# SD.net
KiCad netlist of a schematic drawn in Altium Designer
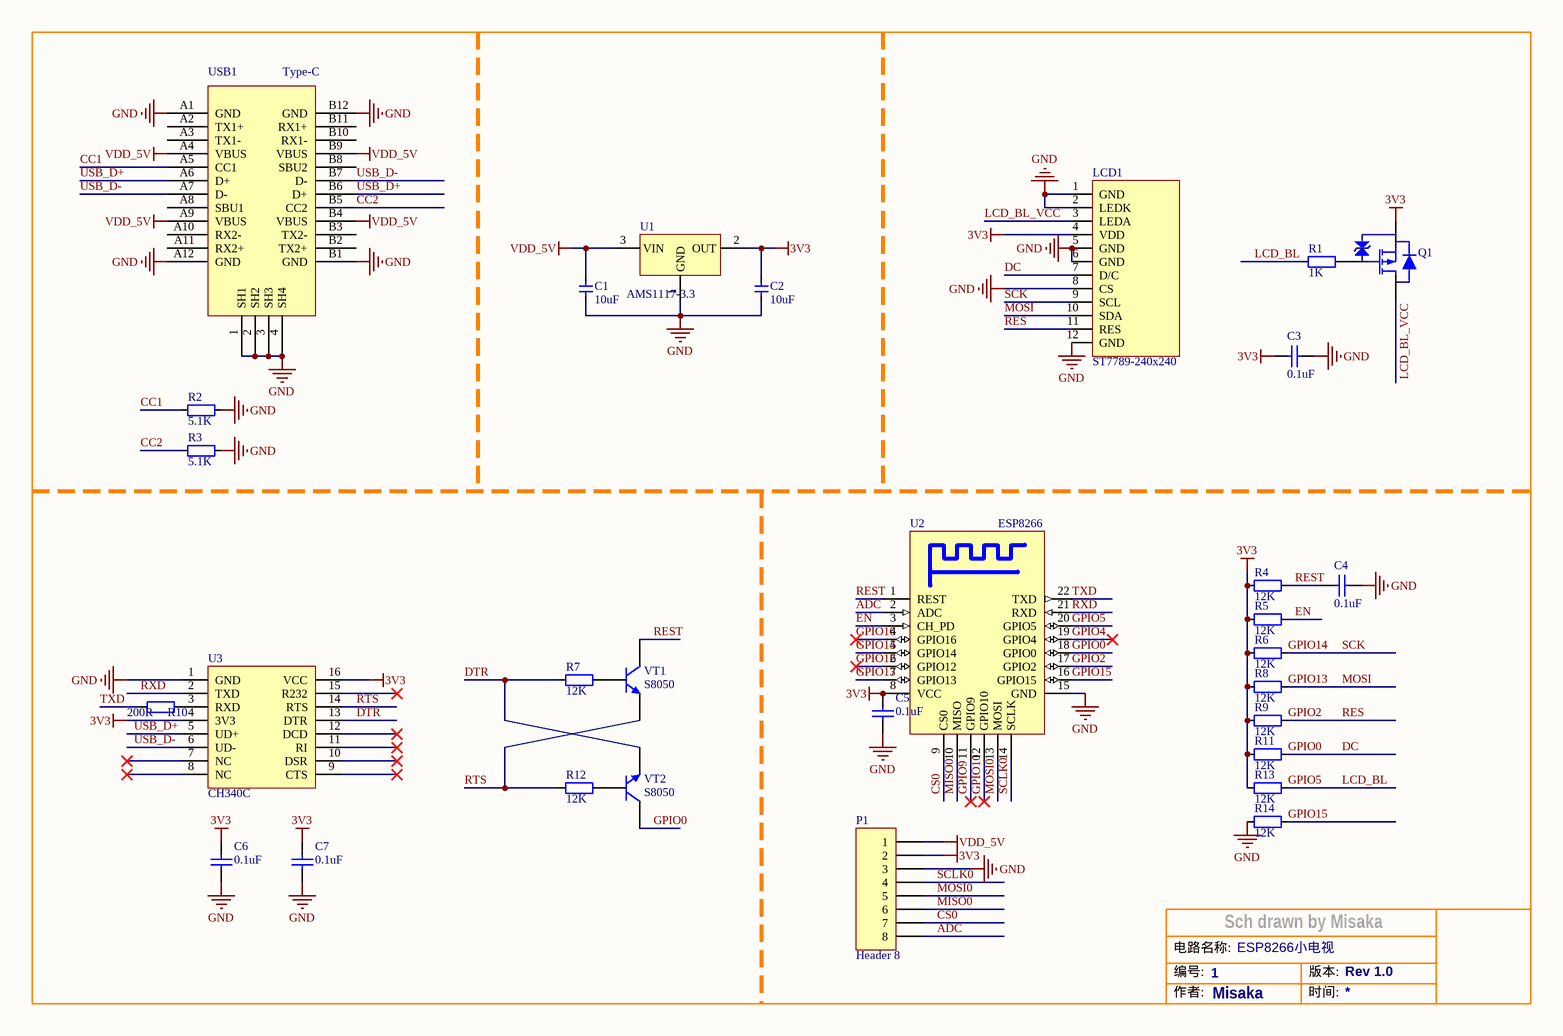
[diagram p0: SD²原理图.SchDoc]

(export (version "E")
  (design (tool "Eeschema 10.0.6"))
  (components
    (comp (ref "C1")
      (value "10uF")
      (footprint "C_0603")
      (description "Capacitor")
      (libsource (lib "MyPcbLib") (part "电容-0402"))
    )
    (comp (ref "C2")
      (value "10uF")
      (footprint "C_0603")
      (description "Capacitor")
      (libsource (lib "MyPcbLib") (part "电容-0402"))
    )
    (comp (ref "C3")
      (value "0.1uF")
      (footprint "C_0603")
      (description "Capacitor")
      (fields (field (name "PUBLISHER") "Altium Limited"))
      (libsource (lib "Miscellaneous Devices") (part "Cap"))
    )
    (comp (ref "C4")
      (value "0.1uF")
      (footprint "C_0603")
      (description "Capacitor")
      (fields (field (name "PUBLISHER") "Altium Limited"))
      (libsource (lib "Miscellaneous Devices") (part "Cap"))
    )
    (comp (ref "C5")
      (value "0.1uF")
      (footprint "C_0603")
      (description "Capacitor")
      (fields (field (name "PUBLISHER") "Altium Limited"))
      (libsource (lib "Miscellaneous Devices") (part "Cap"))
    )
    (comp (ref "C6")
      (value "0.1uF")
      (footprint "C_0603")
      (description "Capacitor")
      (fields (field (name "PUBLISHER") "Altium Limited"))
      (libsource (lib "Miscellaneous Devices") (part "Cap"))
    )
    (comp (ref "C7")
      (value "0.1uF")
      (footprint "C_0603")
      (description "Capacitor")
      (fields (field (name "PUBLISHER") "Altium Limited"))
      (libsource (lib "Miscellaneous Devices") (part "Cap"))
    )
    (comp (ref "LCD1")
      (value "ST7789-240x240")
      (footprint "LCD-240X240-12P")
      (description "显示屏")
      (libsource (lib "mLib") (part "LCD-240x240"))
    )
    (comp (ref "P1")
      (value "Header 8")
      (footprint "FFC_0.5_8")
      (description "Header, 8-Pin")
      (fields (field (name "PUBLISHER") "Altium Limited"))
      (libsource (lib "Miscellaneous Connectors") (part "Header 8"))
    )
    (comp (ref "Q1")
      (value "AO3415A")
      (footprint "SOT-23-y")
      (description "MOSFET")
      (fields (field (name "PUBLISHER") "Altium Limited"))
      (libsource (lib "MyPcbLib") (part "AO3415A"))
    )
    (comp (ref "R1")
      (value "1K")
      (footprint "R_0603")
      (description "Resistor")
      (libsource (lib "") (part "电阻-0402_2"))
    )
    (comp (ref "R2")
      (value "5.1K")
      (footprint "R_0603")
      (description "Resistor")
      (libsource (lib "MyPcbLib") (part "电阻-0402"))
    )
    (comp (ref "R3")
      (value "5.1K")
      (footprint "R_0603")
      (description "Resistor")
      (libsource (lib "MyPcbLib") (part "电阻-0402"))
    )
    (comp (ref "R4")
      (value "12K")
      (footprint "R_0603")
      (description "Resistor")
      (libsource (lib "MyPcbLib") (part "电阻-0402"))
    )
    (comp (ref "R5")
      (value "12K")
      (footprint "R_0603")
      (description "Resistor")
      (libsource (lib "MyPcbLib") (part "电阻-0402"))
    )
    (comp (ref "R6")
      (value "12K")
      (footprint "R_0603")
      (description "Resistor")
      (libsource (lib "MyPcbLib") (part "电阻-0402"))
    )
    (comp (ref "R7")
      (value "12K")
      (footprint "R_0603")
      (description "Resistor")
      (libsource (lib "MyPcbLib") (part "电阻-0402"))
    )
    (comp (ref "R8")
      (value "12K")
      (footprint "R_0603")
      (description "Resistor")
      (libsource (lib "MyPcbLib") (part "电阻-0402"))
    )
    (comp (ref "R9")
      (value "12K")
      (footprint "R_0603")
      (description "Resistor")
      (libsource (lib "MyPcbLib") (part "电阻-0402"))
    )
    (comp (ref "R10")
      (value "200R")
      (footprint "R_0603")
      (description "Resistor")
      (libsource (lib "") (part "电阻-0402_1"))
    )
    (comp (ref "R11")
      (value "12K")
      (footprint "R_0603")
      (description "Resistor")
      (libsource (lib "MyPcbLib") (part "电阻-0402"))
    )
    (comp (ref "R12")
      (value "12K")
      (footprint "R_0603")
      (description "Resistor")
      (libsource (lib "MyPcbLib") (part "电阻-0402"))
    )
    (comp (ref "R13")
      (value "12K")
      (footprint "R_0603")
      (description "Resistor")
      (libsource (lib "MyPcbLib") (part "电阻-0402"))
    )
    (comp (ref "R14")
      (value "12K")
      (footprint "R_0603")
      (description "Resistor")
      (libsource (lib "MyPcbLib") (part "电阻-0402"))
    )
    (comp (ref "U1") (value "AMS1117-3.3") (footprint "SOT223_y") (libsource (lib "数控电源") (part "LM317M")))
    (comp (ref "U2") (value "ESP8266") (footprint "8266") (libsource (lib "Misaka") (part "ESP8266")))
    (comp (ref "U3") (value "CH340C") (footprint "SOP16N_N") (libsource (lib "Misaka") (part "CH340C")))
    (comp (ref "USB1")
      (value "Type-C")
      (footprint "Misaka:Type-C-TOP")
      (libsource (lib "MyPcbLib") (part "USB-Type-C-TOP"))
    )
    (comp (ref "VT1")
      (value "S8050")
      (footprint "SOT-23-y")
      (description "Surface mount NPN transistor, package SOT-23")
      (libsource (lib "MyPcbLib") (part "SMT_TRIODE_NPN"))
    )
    (comp (ref "VT2")
      (value "S8050")
      (footprint "SOT-23-y")
      (description "Surface mount NPN transistor, package SOT-23")
      (libsource (lib "MyPcbLib") (part "SMT_TRIODE_NPN"))
    )
  )
  (nets
    (net (code "1") (name "/ADC") (class "Default")
      (node (ref "P1") (pin "8") (pinfunction "8_8") (pintype "passive"))
      (node (ref "U2") (pin "2") (pinfunction "ADC_2") (pintype "input"))
    )
    (net (code "2") (name "/CC1") (class "Default")
      (node (ref "R2") (pin "1") (pinfunction "1_1") (pintype "passive"))
      (node (ref "USB1") (pin "A5") (pinfunction "CC1_A5") (pintype "passive"))
    )
    (net (code "3") (name "/CC2") (class "Default")
      (node (ref "R3") (pin "1") (pinfunction "1_1") (pintype "passive"))
      (node (ref "USB1") (pin "B5") (pinfunction "CC2_B5") (pintype "passive"))
    )
    (net (code "4") (name "/CS0") (class "Default")
      (node (ref "P1") (pin "7") (pinfunction "7_7") (pintype "passive"))
      (node (ref "U2") (pin "9") (pinfunction "CS0_9") (pintype "passive"))
    )
    (net (code "5") (name "/DC") (class "Default")
      (node (ref "LCD1") (pin "7") (pinfunction "D/C_7") (pintype "passive"))
      (node (ref "R11") (pin "2") (pinfunction "2_2") (pintype "passive"))
      (node (ref "U2") (pin "18") (pinfunction "GPIO0_18") (pintype "bidirectional"))
      (node (ref "VT2") (pin "3") (pinfunction "C_3") (pintype "passive"))
    )
    (net (code "6") (name "/DTR") (class "Default")
      (node (ref "R7") (pin "1") (pinfunction "1_1") (pintype "passive"))
      (node (ref "U3") (pin "13") (pinfunction "DTR_13") (pintype "passive"))
      (node (ref "VT2") (pin "2") (pinfunction "E_2") (pintype "passive"))
    )
    (net (code "7") (name "/EN") (class "Default")
      (node (ref "R5") (pin "2") (pinfunction "2_2") (pintype "passive"))
      (node (ref "U2") (pin "3") (pinfunction "CH_PD_3") (pintype "input"))
    )
    (net (code "8") (name "/GPIO2") (class "Default")
      (node (ref "LCD1") (pin "11") (pinfunction "RES_11") (pintype "passive"))
      (node (ref "R9") (pin "2") (pinfunction "2_2") (pintype "passive"))
      (node (ref "U2") (pin "17") (pinfunction "GPIO2_17") (pintype "bidirectional"))
    )
    (net (code "9") (name "/GPIO4") (class "Default")
      (node (ref "U2") (pin "19") (pinfunction "GPIO4_19") (pintype "bidirectional+no_connect"))
    )
    (net (code "10") (name "/GPIO5") (class "Default")
      (node (ref "R1") (pin "1") (pinfunction "1_1") (pintype "passive"))
      (node (ref "R13") (pin "2") (pinfunction "2_2") (pintype "passive"))
      (node (ref "U2") (pin "20") (pinfunction "GPIO5_20") (pintype "bidirectional"))
    )
    (net (code "11") (name "/GPIO9") (class "Default")
      (node (ref "U2") (pin "11") (pinfunction "GPIO9_11") (pintype "passive+no_connect"))
    )
    (net (code "12") (name "/GPIO10") (class "Default")
      (node (ref "U2") (pin "12") (pinfunction "GPIO10_12") (pintype "passive+no_connect"))
    )
    (net (code "13") (name "/GPIO12") (class "Default")
      (node (ref "U2") (pin "6") (pinfunction "GPIO12_6") (pintype "bidirectional+no_connect"))
    )
    (net (code "14") (name "/GPIO13") (class "Default")
      (node (ref "LCD1") (pin "10") (pinfunction "SDA_10") (pintype "passive"))
      (node (ref "R8") (pin "2") (pinfunction "2_2") (pintype "passive"))
      (node (ref "U2") (pin "7") (pinfunction "GPIO13_7") (pintype "bidirectional"))
    )
    (net (code "15") (name "/GPIO14") (class "Default")
      (node (ref "LCD1") (pin "9") (pinfunction "SCL_9") (pintype "passive"))
      (node (ref "R6") (pin "2") (pinfunction "2_2") (pintype "passive"))
      (node (ref "U2") (pin "5") (pinfunction "GPIO14_5") (pintype "bidirectional"))
    )
    (net (code "16") (name "/GPIO15") (class "Default")
      (node (ref "R14") (pin "2") (pinfunction "2_2") (pintype "passive"))
      (node (ref "U2") (pin "16") (pinfunction "GPIO15_16") (pintype "bidirectional"))
    )
    (net (code "17") (name "/GPIO16") (class "Default")
      (node (ref "U2") (pin "4") (pinfunction "GPIO16_4") (pintype "bidirectional+no_connect"))
    )
    (net (code "18") (name "/LCD_BL_VCC") (class "Default")
      (node (ref "LCD1") (pin "3") (pinfunction "LEDA_3") (pintype "passive"))
      (node (ref "Q1") (pin "3") (pinfunction "D_3") (pintype "passive"))
    )
    (net (code "19") (name "/MISO0") (class "Default")
      (node (ref "P1") (pin "6") (pinfunction "6_6") (pintype "passive"))
      (node (ref "U2") (pin "10") (pinfunction "MISO_10") (pintype "passive"))
    )
    (net (code "20") (name "/MOSI0") (class "Default")
      (node (ref "P1") (pin "5") (pinfunction "5_5") (pintype "passive"))
      (node (ref "U2") (pin "13") (pinfunction "MOSI_13") (pintype "passive"))
    )
    (net (code "21") (name "/REST") (class "Default")
      (node (ref "C4") (pin "2") (pinfunction "2_2") (pintype "passive"))
      (node (ref "R4") (pin "2") (pinfunction "2_2") (pintype "passive"))
      (node (ref "U2") (pin "1") (pinfunction "REST_1") (pintype "passive"))
      (node (ref "VT1") (pin "3") (pinfunction "C_3") (pintype "passive"))
    )
    (net (code "22") (name "/RTS") (class "Default")
      (node (ref "R12") (pin "1") (pinfunction "1_1") (pintype "passive"))
      (node (ref "U3") (pin "14") (pinfunction "RTS_14") (pintype "passive"))
      (node (ref "VT1") (pin "2") (pinfunction "E_2") (pintype "passive"))
    )
    (net (code "23") (name "/RXD") (class "Default")
      (node (ref "U2") (pin "21") (pinfunction "RXD_21") (pintype "input"))
      (node (ref "U3") (pin "2") (pinfunction "TXD_2") (pintype "passive"))
    )
    (net (code "24") (name "/SCLK0") (class "Default")
      (node (ref "P1") (pin "4") (pinfunction "4_4") (pintype "passive"))
      (node (ref "U2") (pin "14") (pinfunction "SCLK_14") (pintype "passive"))
    )
    (net (code "25") (name "/TXD") (class "Default")
      (node (ref "R10") (pin "2") (pinfunction "2_2") (pintype "passive"))
      (node (ref "U2") (pin "22") (pinfunction "TXD_22") (pintype "output"))
    )
    (net (code "26") (name "/USB_D+") (class "Default")
      (node (ref "U3") (pin "5") (pinfunction "UD+_5") (pintype "passive"))
      (node (ref "USB1") (pin "A6") (pinfunction "D+_A6") (pintype "passive"))
      (node (ref "USB1") (pin "B6") (pinfunction "D+_B6") (pintype "passive"))
    )
    (net (code "27") (name "/USB_D-") (class "Default")
      (node (ref "U3") (pin "6") (pinfunction "UD-_6") (pintype "passive"))
      (node (ref "USB1") (pin "A7") (pinfunction "D-_A7") (pintype "passive"))
      (node (ref "USB1") (pin "B7") (pinfunction "D-_B7") (pintype "passive"))
    )
    (net (code "28") (name "3V3") (class "Default")
      (node (ref "C2") (pin "2") (pinfunction "2_2") (pintype "passive"))
      (node (ref "C3") (pin "2") (pinfunction "2_2") (pintype "passive"))
      (node (ref "C5") (pin "2") (pinfunction "2_2") (pintype "passive"))
      (node (ref "C6") (pin "2") (pinfunction "2_2") (pintype "passive"))
      (node (ref "C7") (pin "2") (pinfunction "2_2") (pintype "passive"))
      (node (ref "LCD1") (pin "4") (pinfunction "VDD_4") (pintype "passive"))
      (node (ref "P1") (pin "2") (pinfunction "2_2") (pintype "passive"))
      (node (ref "Q1") (pin "2") (pinfunction "S_2") (pintype "passive"))
      (node (ref "R11") (pin "1") (pinfunction "1_1") (pintype "passive"))
      (node (ref "R13") (pin "1") (pinfunction "1_1") (pintype "passive"))
      (node (ref "R4") (pin "1") (pinfunction "1_1") (pintype "passive"))
      (node (ref "R5") (pin "1") (pinfunction "1_1") (pintype "passive"))
      (node (ref "R6") (pin "1") (pinfunction "1_1") (pintype "passive"))
      (node (ref "R8") (pin "1") (pinfunction "1_1") (pintype "passive"))
      (node (ref "R9") (pin "1") (pinfunction "1_1") (pintype "passive"))
      (node (ref "U1") (pin "2") (pinfunction "OUT_2") (pintype "passive"))
      (node (ref "U2") (pin "8") (pinfunction "VCC_8") (pintype "power_in"))
      (node (ref "U3") (pin "16") (pinfunction "VCC_16") (pintype "passive"))
      (node (ref "U3") (pin "4") (pinfunction "3V3_4") (pintype "passive"))
    )
    (net (code "29") (name "GND") (class "Default")
      (node (ref "C1") (pin "1") (pinfunction "1_1") (pintype "passive"))
      (node (ref "C2") (pin "1") (pinfunction "1_1") (pintype "passive"))
      (node (ref "C3") (pin "1") (pinfunction "1_1") (pintype "passive"))
      (node (ref "C4") (pin "1") (pinfunction "1_1") (pintype "passive"))
      (node (ref "C5") (pin "1") (pinfunction "1_1") (pintype "passive"))
      (node (ref "C6") (pin "1") (pinfunction "1_1") (pintype "passive"))
      (node (ref "C7") (pin "1") (pinfunction "1_1") (pintype "passive"))
      (node (ref "LCD1") (pin "1") (pinfunction "GND_1") (pintype "passive"))
      (node (ref "LCD1") (pin "12") (pinfunction "GND_12") (pintype "passive"))
      (node (ref "LCD1") (pin "2") (pinfunction "LEDK_2") (pintype "passive"))
      (node (ref "LCD1") (pin "5") (pinfunction "GND_5") (pintype "passive"))
      (node (ref "LCD1") (pin "6") (pinfunction "GND_6") (pintype "passive"))
      (node (ref "LCD1") (pin "8") (pinfunction "CS_8") (pintype "passive"))
      (node (ref "P1") (pin "3") (pinfunction "3_3") (pintype "passive"))
      (node (ref "R14") (pin "1") (pinfunction "1_1") (pintype "passive"))
      (node (ref "R2") (pin "2") (pinfunction "2_2") (pintype "passive"))
      (node (ref "R3") (pin "2") (pinfunction "2_2") (pintype "passive"))
      (node (ref "U1") (pin "1") (pinfunction "GND_1") (pintype "passive"))
      (node (ref "U2") (pin "15") (pinfunction "GND_15") (pintype "power_in"))
      (node (ref "U3") (pin "1") (pinfunction "GND_1") (pintype "passive"))
      (node (ref "USB1") (pin "1") (pinfunction "SH1_1") (pintype "passive"))
      (node (ref "USB1") (pin "2") (pinfunction "SH2_2") (pintype "passive"))
      (node (ref "USB1") (pin "3") (pinfunction "SH3_3") (pintype "passive"))
      (node (ref "USB1") (pin "4") (pinfunction "SH4_4") (pintype "passive"))
      (node (ref "USB1") (pin "A1") (pinfunction "GND_A1") (pintype "passive"))
      (node (ref "USB1") (pin "A12") (pinfunction "GND_A12") (pintype "passive"))
      (node (ref "USB1") (pin "B1") (pinfunction "GND_B1") (pintype "passive"))
      (node (ref "USB1") (pin "B12") (pinfunction "GND_B12") (pintype "passive"))
    )
    (net (code "30") (name "Net-(Q1-G)") (class "Default")
      (node (ref "Q1") (pin "1") (pinfunction "G_1") (pintype "passive"))
      (node (ref "R1") (pin "2") (pinfunction "2_2") (pintype "passive"))
    )
    (net (code "31") (name "Net-(U3-RXD)") (class "Default")
      (node (ref "R10") (pin "1") (pinfunction "1_1") (pintype "passive"))
      (node (ref "U3") (pin "3") (pinfunction "RXD_3") (pintype "passive"))
    )
    (net (code "32") (name "Net-(VT1-B)") (class "Default")
      (node (ref "R7") (pin "2") (pinfunction "2_2") (pintype "passive"))
      (node (ref "VT1") (pin "1") (pinfunction "B_1") (pintype "passive"))
    )
    (net (code "33") (name "Net-(VT2-B)") (class "Default")
      (node (ref "R12") (pin "2") (pinfunction "2_2") (pintype "passive"))
      (node (ref "VT2") (pin "1") (pinfunction "B_1") (pintype "passive"))
    )
    (net (code "34") (name "VDD_5V") (class "Default")
      (node (ref "C1") (pin "2") (pinfunction "2_2") (pintype "passive"))
      (node (ref "P1") (pin "1") (pinfunction "1_1") (pintype "passive"))
      (node (ref "U1") (pin "3") (pinfunction "VIN_3") (pintype "passive"))
      (node (ref "USB1") (pin "A4") (pinfunction "VBUS_A4") (pintype "passive"))
      (node (ref "USB1") (pin "A9") (pinfunction "VBUS_A9") (pintype "passive"))
      (node (ref "USB1") (pin "B4") (pinfunction "VBUS_B4") (pintype "passive"))
      (node (ref "USB1") (pin "B9") (pinfunction "VBUS_B9") (pintype "passive"))
    )
    (net (code "35") (name "unconnected-(U3-CTS-Pad9)") (class "Default")
      (node (ref "U3") (pin "9") (pinfunction "CTS_9") (pintype "passive+no_connect"))
    )
    (net (code "36") (name "unconnected-(U3-DCD-Pad12)") (class "Default")
      (node (ref "U3") (pin "12") (pinfunction "DCD_12") (pintype "passive+no_connect"))
    )
    (net (code "37") (name "unconnected-(U3-DSR-Pad10)") (class "Default")
      (node (ref "U3") (pin "10") (pinfunction "DSR_10") (pintype "passive+no_connect"))
    )
    (net (code "38") (name "unconnected-(U3-NC-Pad7)") (class "Default")
      (node (ref "U3") (pin "7") (pinfunction "NC_7") (pintype "passive+no_connect"))
    )
    (net (code "39") (name "unconnected-(U3-NC-Pad8)") (class "Default")
      (node (ref "U3") (pin "8") (pinfunction "NC_8") (pintype "passive+no_connect"))
    )
    (net (code "40") (name "unconnected-(U3-R232-Pad15)") (class "Default")
      (node (ref "U3") (pin "15") (pinfunction "R232_15") (pintype "passive+no_connect"))
    )
    (net (code "41") (name "unconnected-(U3-RI-Pad11)") (class "Default")
      (node (ref "U3") (pin "11") (pinfunction "RI_11") (pintype "passive+no_connect"))
    )
    (net (code "42") (name "unconnected-(USB1-RX1+-PadB11)") (class "Default")
      (node (ref "USB1") (pin "B11") (pinfunction "RX1+_B11") (pintype "passive"))
    )
    (net (code "43") (name "unconnected-(USB1-RX1--PadB10)") (class "Default")
      (node (ref "USB1") (pin "B10") (pinfunction "RX1-_B10") (pintype "passive"))
    )
    (net (code "44") (name "unconnected-(USB1-RX2+-PadA11)") (class "Default")
      (node (ref "USB1") (pin "A11") (pinfunction "RX2+_A11") (pintype "passive"))
    )
    (net (code "45") (name "unconnected-(USB1-RX2--PadA10)") (class "Default")
      (node (ref "USB1") (pin "A10") (pinfunction "RX2-_A10") (pintype "passive"))
    )
    (net (code "46") (name "unconnected-(USB1-SBU1-PadA8)") (class "Default")
      (node (ref "USB1") (pin "A8") (pinfunction "SBU1_A8") (pintype "passive"))
    )
    (net (code "47") (name "unconnected-(USB1-SBU2-PadB8)") (class "Default")
      (node (ref "USB1") (pin "B8") (pinfunction "SBU2_B8") (pintype "passive"))
    )
    (net (code "48") (name "unconnected-(USB1-TX1+-PadA2)") (class "Default")
      (node (ref "USB1") (pin "A2") (pinfunction "TX1+_A2") (pintype "passive"))
    )
    (net (code "49") (name "unconnected-(USB1-TX1--PadA3)") (class "Default")
      (node (ref "USB1") (pin "A3") (pinfunction "TX1-_A3") (pintype "passive"))
    )
    (net (code "50") (name "unconnected-(USB1-TX2+-PadB2)") (class "Default")
      (node (ref "USB1") (pin "B2") (pinfunction "TX2+_B2") (pintype "passive"))
    )
    (net (code "51") (name "unconnected-(USB1-TX2--PadB3)") (class "Default")
      (node (ref "USB1") (pin "B3") (pinfunction "TX2-_B3") (pintype "passive"))
    )
  )
)
